# GongxunZhukong.net
KiCad netlist of a schematic drawn in Altium Designer
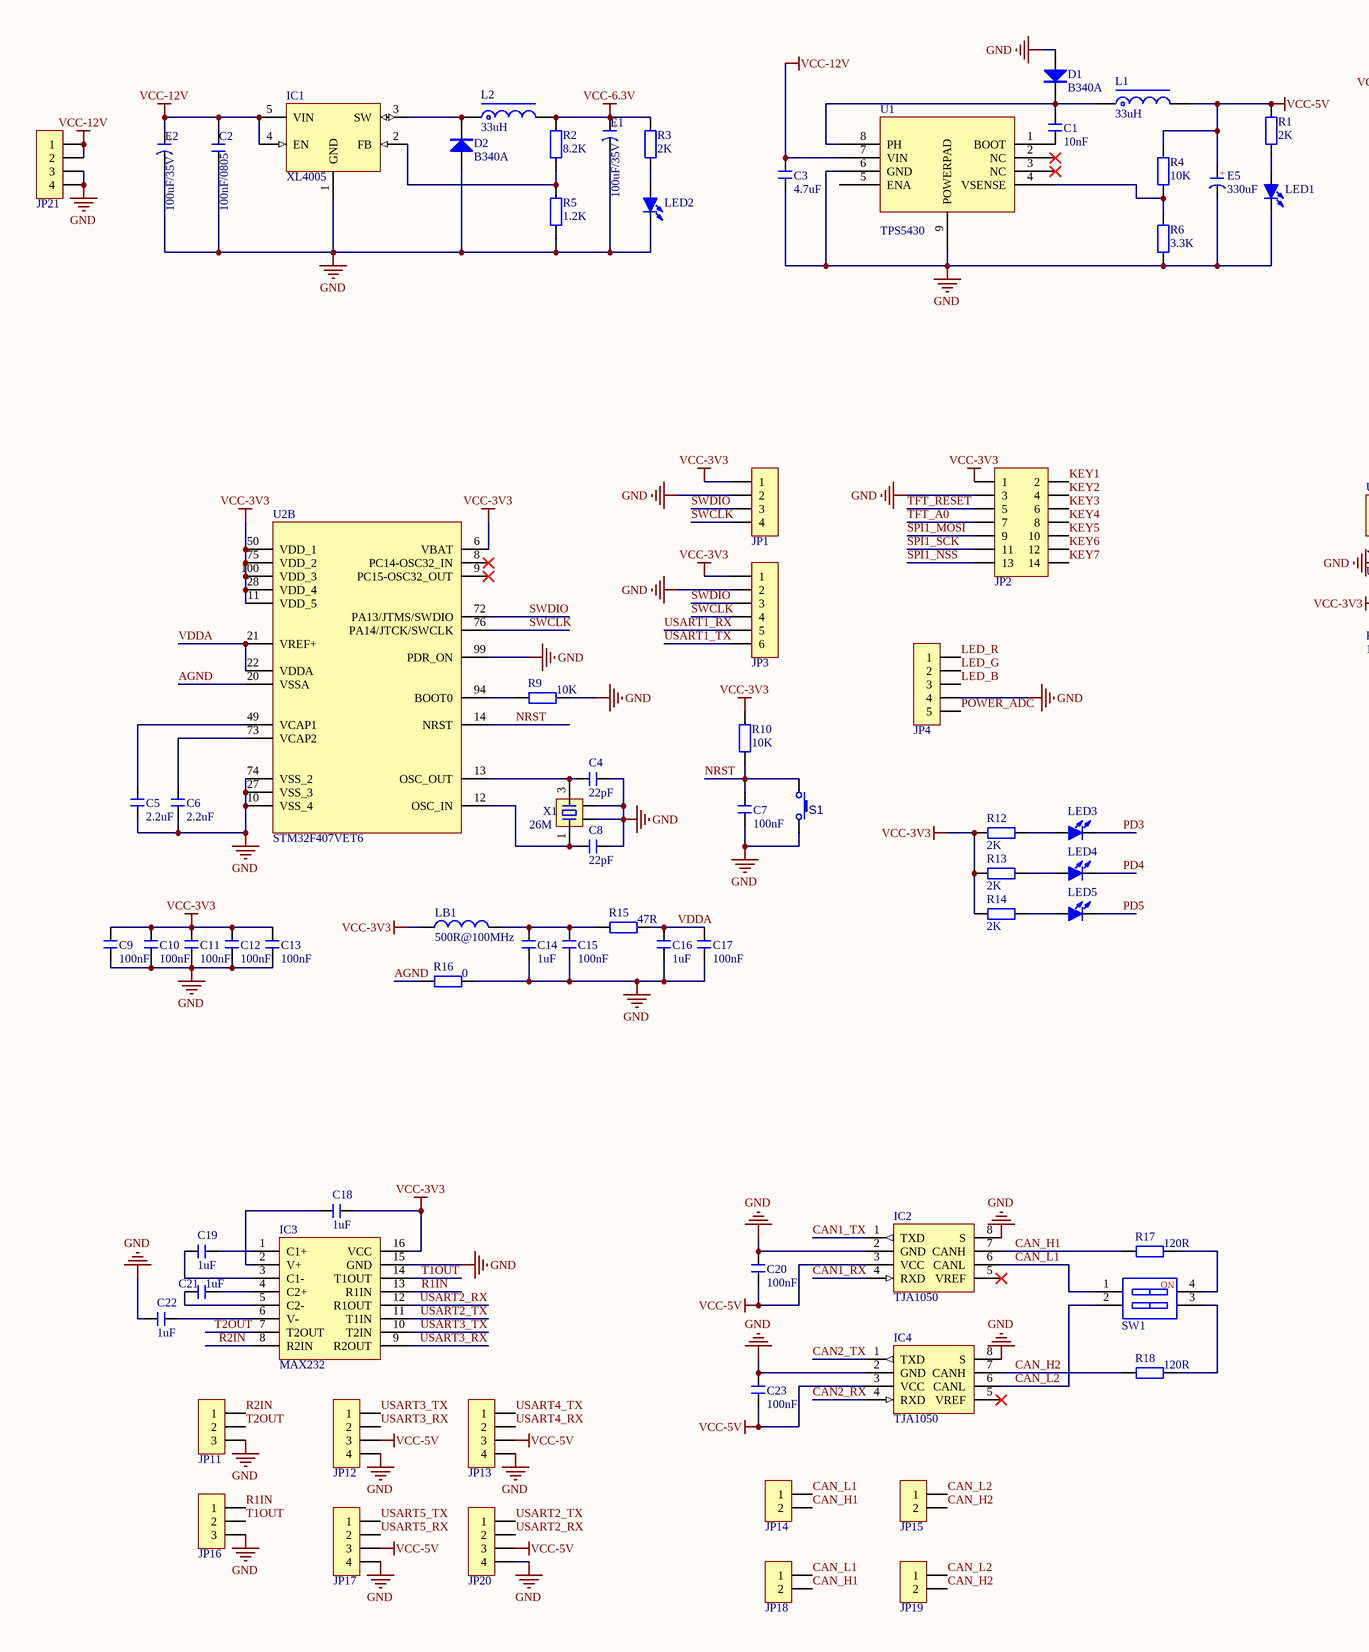
[diagram p0: GongxunZhukong.SchDoc, left]
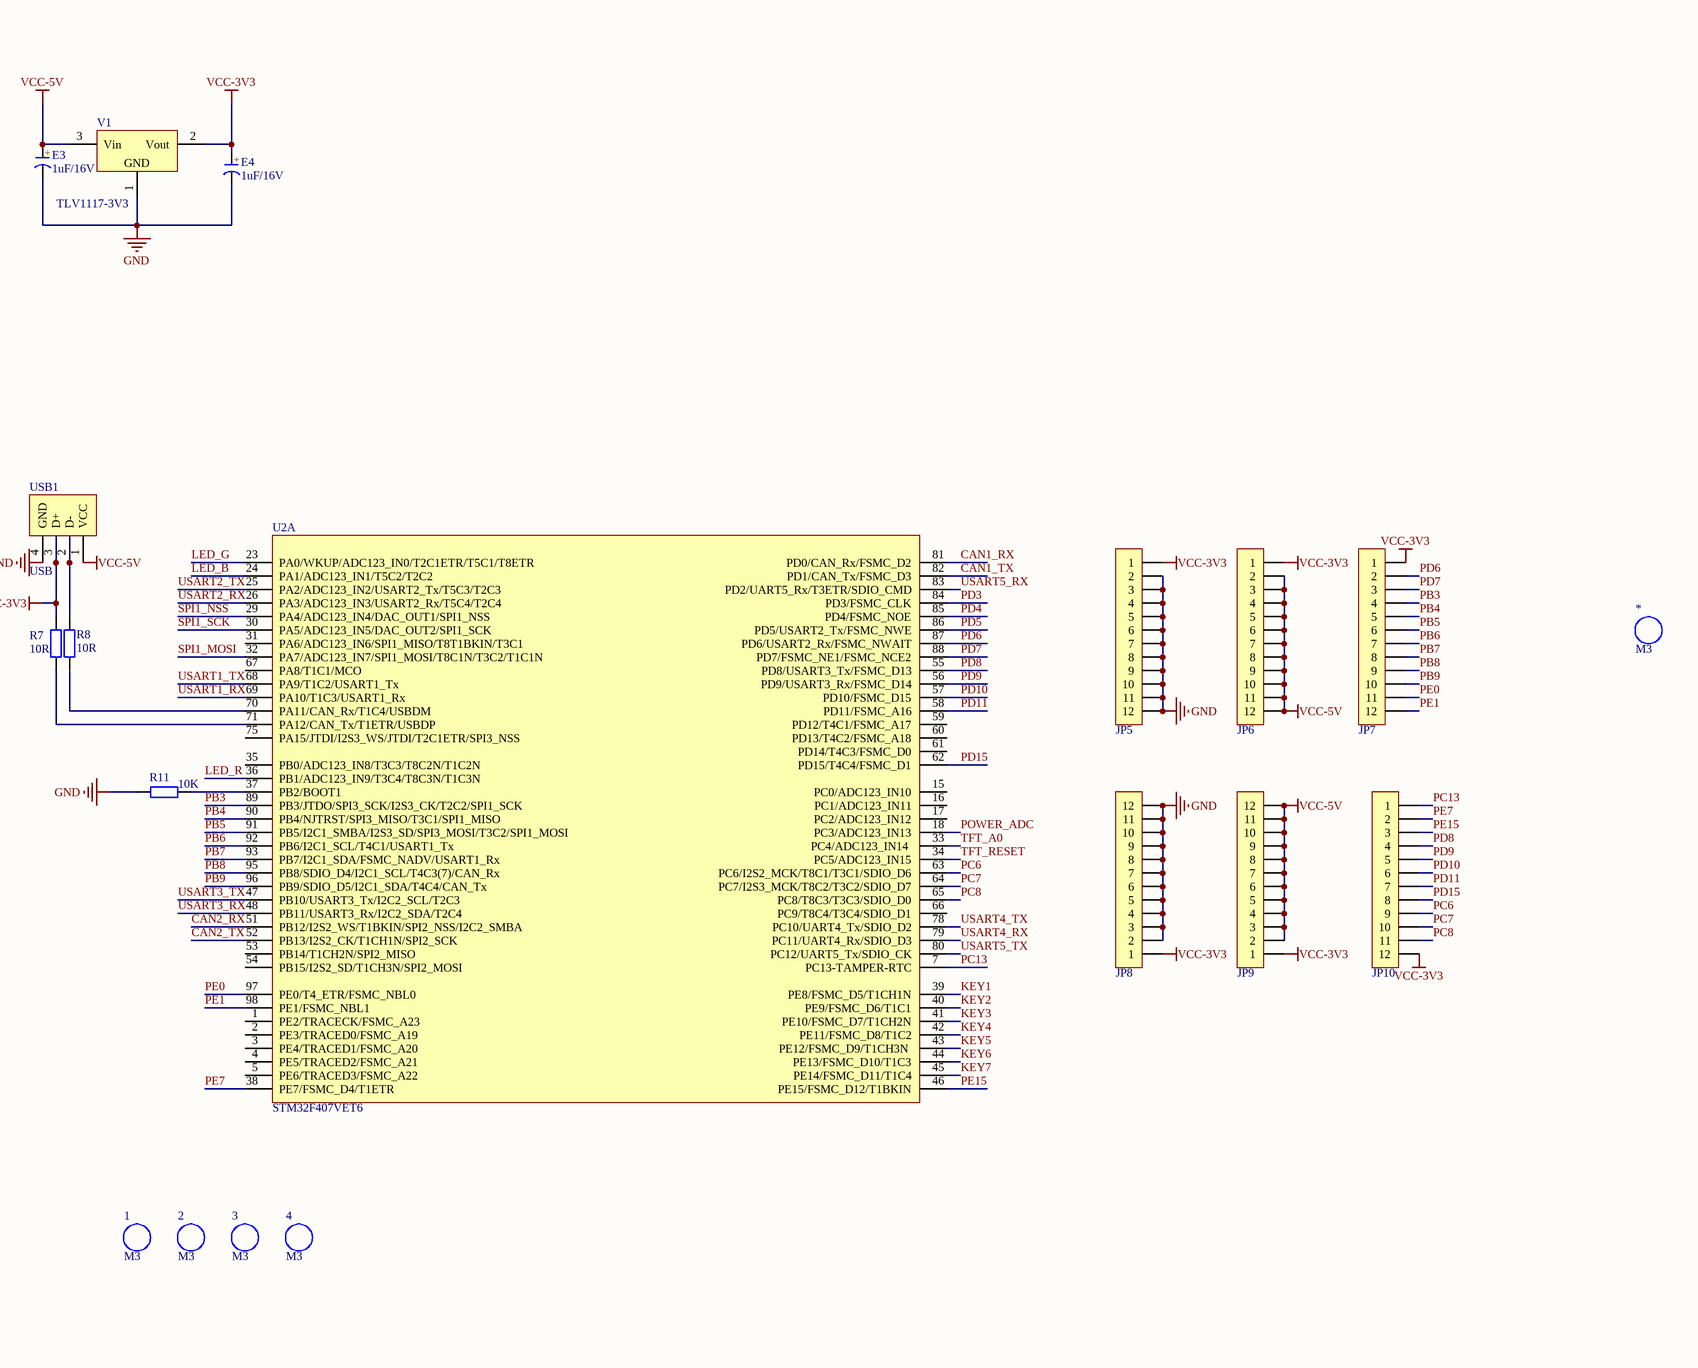
[diagram p1: GongxunZhukong.SchDoc, right]

(export (version "E")
  (design (tool "Eeschema 10.0.6"))
  (components
    (comp (ref "*")
      (value "M3")
      (footprint "M3 125X200")
      (description "铜柱孔")
      (libsource (lib "15.1 - 未分类器件") (part "M3"))
    )
    (comp (ref "1")
      (value "M3")
      (footprint "M3 125X200")
      (description "铜柱孔")
      (libsource (lib "15.1 - 未分类器件") (part "M3"))
    )
    (comp (ref "2")
      (value "M3")
      (footprint "M3 125X200")
      (description "铜柱孔")
      (libsource (lib "15.1 - 未分类器件") (part "M3"))
    )
    (comp (ref "3")
      (value "M3")
      (footprint "M3 125X200")
      (description "铜柱孔")
      (libsource (lib "15.1 - 未分类器件") (part "M3"))
    )
    (comp (ref "4")
      (value "M3")
      (footprint "M3 125X200")
      (description "铜柱孔")
      (libsource (lib "15.1 - 未分类器件") (part "M3"))
    )
    (comp (ref "C1")
      (value "10nF")
      (footprint "C 0603_M")
      (description "无极性贴片电容")
      (libsource (lib "3.1   - 电阻-电容-电感") (part "C"))
    )
    (comp (ref "C2")
      (value "100nF/0805")
      (footprint "C 0805_L")
      (description "无极性贴片电容")
      (libsource (lib "3.1   - 电阻-电容-电感") (part "C"))
    )
    (comp (ref "C3")
      (value "4.7uF")
      (footprint "C 0603_M")
      (description "无极性贴片电容")
      (libsource (lib "3.1   - 电阻-电容-电感") (part "C"))
    )
    (comp (ref "C4")
      (value "22pF")
      (footprint "C 0603_M")
      (description "无极性贴片电容")
      (libsource (lib "3.1   - 电阻-电容-电感") (part "C"))
    )
    (comp (ref "C5")
      (value "2.2uF")
      (footprint "C 0603_M")
      (description "无极性贴片电容")
      (libsource (lib "3.1   - 电阻-电容-电感") (part "C"))
    )
    (comp (ref "C6")
      (value "2.2uF")
      (footprint "C 0603_M")
      (description "无极性贴片电容")
      (libsource (lib "3.1   - 电阻-电容-电感") (part "C"))
    )
    (comp (ref "C7")
      (value "100nF")
      (footprint "C 0603_M")
      (description "无极性贴片电容")
      (libsource (lib "3.1   - 电阻-电容-电感") (part "C"))
    )
    (comp (ref "C8")
      (value "22pF")
      (footprint "C 0603_M")
      (description "无极性贴片电容")
      (libsource (lib "3.1   - 电阻-电容-电感") (part "C"))
    )
    (comp (ref "C9")
      (value "100nF")
      (footprint "C 0603_M")
      (description "无极性贴片电容")
      (libsource (lib "3.1   - 电阻-电容-电感") (part "C"))
    )
    (comp (ref "C10")
      (value "100nF")
      (footprint "C 0603_M")
      (description "无极性贴片电容")
      (libsource (lib "3.1   - 电阻-电容-电感") (part "C"))
    )
    (comp (ref "C11")
      (value "100nF")
      (footprint "C 0603_M")
      (description "无极性贴片电容")
      (libsource (lib "3.1   - 电阻-电容-电感") (part "C"))
    )
    (comp (ref "C12")
      (value "100nF")
      (footprint "C 0603_M")
      (description "无极性贴片电容")
      (libsource (lib "3.1   - 电阻-电容-电感") (part "C"))
    )
    (comp (ref "C13")
      (value "100nF")
      (footprint "C 0603_M")
      (description "无极性贴片电容")
      (libsource (lib "3.1   - 电阻-电容-电感") (part "C"))
    )
    (comp (ref "C14")
      (value "1uF")
      (footprint "C 0603_M")
      (description "无极性贴片电容")
      (libsource (lib "3.1   - 电阻-电容-电感") (part "C"))
    )
    (comp (ref "C15")
      (value "100nF")
      (footprint "C 0603_M")
      (description "无极性贴片电容")
      (libsource (lib "3.1   - 电阻-电容-电感") (part "C"))
    )
    (comp (ref "C16")
      (value "1uF")
      (footprint "C 0603_M")
      (description "无极性贴片电容")
      (libsource (lib "3.1   - 电阻-电容-电感") (part "C"))
    )
    (comp (ref "C17")
      (value "100nF")
      (footprint "C 0603_M")
      (description "无极性贴片电容")
      (libsource (lib "3.1   - 电阻-电容-电感") (part "C"))
    )
    (comp (ref "C18")
      (value "1uF")
      (footprint "C 0603_M")
      (description "无极性贴片电容")
      (libsource (lib "3.1   - 电阻-电容-电感") (part "C"))
    )
    (comp (ref "C19")
      (value "1uF")
      (footprint "C 0603_M")
      (description "无极性贴片电容")
      (libsource (lib "3.1   - 电阻-电容-电感") (part "C"))
    )
    (comp (ref "C20")
      (value "100nF")
      (footprint "C 0603_M")
      (description "无极性贴片电容")
      (libsource (lib "3.1   - 电阻-电容-电感") (part "C"))
    )
    (comp (ref "C21")
      (value "1uF")
      (footprint "C 0603_M")
      (description "无极性贴片电容")
      (libsource (lib "3.1   - 电阻-电容-电感") (part "C"))
    )
    (comp (ref "C22")
      (value "1uF")
      (footprint "C 0603_M")
      (description "无极性贴片电容")
      (libsource (lib "3.1   - 电阻-电容-电感") (part "C"))
    )
    (comp (ref "C23")
      (value "100nF")
      (footprint "C 0603_M")
      (description "无极性贴片电容")
      (libsource (lib "3.1   - 电阻-电容-电感") (part "C"))
    )
    (comp (ref "D1")
      (value "B340A")
      (footprint "SMA")
      (description "整流二极管")
      (libsource (lib "8.1   - 二极管-整流桥") (part "M7"))
    )
    (comp (ref "D2")
      (value "B340A")
      (footprint "SMA")
      (description "整流二极管")
      (libsource (lib "8.1   - 二极管-整流桥") (part "M7"))
    )
    (comp (ref "E1")
      (value "100uF/35V")
      (footprint "CM A(3*5.4)")
      (description "贴片电解电容")
      (libsource (lib "3.1   - 电阻-电容-电感") (part "C-CM"))
    )
    (comp (ref "E2")
      (value "100uF/35V")
      (footprint "CM A(3*5.4)")
      (description "贴片电解电容")
      (libsource (lib "3.1   - 电阻-电容-电感") (part "C-CM"))
    )
    (comp (ref "E3")
      (value "1uF/16V")
      (footprint "CD A(3216)")
      (description "贴片钽电容")
      (libsource (lib "3.1   - 电阻-电容-电感") (part "C-CD"))
    )
    (comp (ref "E4")
      (value "1uF/16V")
      (footprint "CD A(3216)")
      (description "贴片钽电容")
      (libsource (lib "3.1   - 电阻-电容-电感") (part "C-CD"))
    )
    (comp (ref "E5")
      (value "330uF")
      (footprint "CM D(6.3*7.7)")
      (description "贴片电解电容")
      (libsource (lib "3.1   - 电阻-电容-电感") (part "C-CM"))
    )
    (comp (ref "IC1")
      (value "XL4005")
      (footprint "TO263-5A")
      (description "DC降压芯片")
      (libsource (lib "1.3   - 电源类芯片") (part "XL4005"))
    )
    (comp (ref "IC2")
      (value "TJA1050")
      (footprint "SOP8_N")
      (description "CAN总线收发芯片")
      (libsource (lib "1.1   - IC芯片") (part "TJA1050"))
    )
    (comp (ref "IC3") (value "MAX232") (footprint "SOP16_N") (libsource (lib "1.1   - IC芯片") (part "MAX232")))
    (comp (ref "IC4")
      (value "TJA1050")
      (footprint "SOP8_N")
      (description "CAN总线收发芯片")
      (libsource (lib "1.1   - IC芯片") (part "TJA1050"))
    )
    (comp (ref "JP1")
      (value "HDR-1X4")
      (footprint "HDR2.54-LI-4P")
      (description "4P接插件")
      (libsource (lib "") (part "Header 4_1"))
    )
    (comp (ref "JP2")
      (value "Header 2X7")
      (footprint "HDR2.54-LI-2x7P")
      (description "7*2P接插件")
      (libsource (lib "4.6   - 接插件-脚距2.54") (part "Header 7X2"))
    )
    (comp (ref "JP3")
      (value "HDR-1X6")
      (footprint "PH2.0-WS-6P")
      (description "6P接插件")
      (libsource (lib "4.5   - 接插件-脚距2.0") (part "Header 6"))
    )
    (comp (ref "JP4")
      (value "HDR-1X5")
      (footprint "PH2.0-WS-5P")
      (description "5P接插件")
      (libsource (lib "4.5   - 接插件-脚距2.0") (part "Header 5"))
    )
    (comp (ref "JP5")
      (value "HDR-1X12")
      (footprint "HDR2.54-LI-12P")
      (description "12P接插件")
      (libsource (lib "") (part "Header 12_1"))
    )
    (comp (ref "JP6")
      (value "HDR-1X12")
      (footprint "HDR2.54-LI-12P")
      (description "12P接插件")
      (libsource (lib "") (part "Header 12_1"))
    )
    (comp (ref "JP7")
      (value "HDR-1X12")
      (footprint "HDR2.54-LI-12P")
      (description "12P接插件")
      (libsource (lib "") (part "Header 12_1"))
    )
    (comp (ref "JP8")
      (value "HDR-1X12")
      (footprint "HDR2.54-LI-12P")
      (description "12P接插件")
      (libsource (lib "4.6   - 接插件-脚距2.54") (part "Header 12"))
    )
    (comp (ref "JP9")
      (value "HDR-1X12")
      (footprint "HDR2.54-LI-12P")
      (description "12P接插件")
      (libsource (lib "4.6   - 接插件-脚距2.54") (part "Header 12"))
    )
    (comp (ref "JP10")
      (value "HDR-1X12")
      (footprint "HDR2.54-LI-12P")
      (description "12P接插件")
      (libsource (lib "") (part "Header 12_1"))
    )
    (comp (ref "JP11")
      (value "HDR-1X3")
      (footprint "PH2.0-WS-3P")
      (description "3P接插件")
      (libsource (lib "4.5   - 接插件-脚距2.0") (part "Header 3"))
    )
    (comp (ref "JP12")
      (value "HDR-1X4")
      (footprint "HDR2.54-LI-4P")
      (description "4P接插件")
      (libsource (lib "4.6   - 接插件-脚距2.54") (part "Header 4"))
    )
    (comp (ref "JP13")
      (value "HDR-1X4")
      (footprint "HDR2.54-LI-4P")
      (description "4P接插件")
      (libsource (lib "4.6   - 接插件-脚距2.54") (part "Header 4"))
    )
    (comp (ref "JP14")
      (value "HDR-1X2")
      (footprint "PH2.0-WS-2P")
      (description "2P接插件")
      (libsource (lib "4.5   - 接插件-脚距2.0") (part "Header 2"))
    )
    (comp (ref "JP15")
      (value "HDR-1X2")
      (footprint "PH2.0-WS-2P")
      (description "2P接插件")
      (libsource (lib "4.5   - 接插件-脚距2.0") (part "Header 2"))
    )
    (comp (ref "JP16")
      (value "HDR-1X3")
      (footprint "PH2.0-WS-3P")
      (description "3P接插件")
      (libsource (lib "4.5   - 接插件-脚距2.0") (part "Header 3"))
    )
    (comp (ref "JP17")
      (value "HDR-1X4")
      (footprint "HDR2.54-LI-4P")
      (description "4P接插件")
      (libsource (lib "4.6   - 接插件-脚距2.54") (part "Header 4"))
    )
    (comp (ref "JP18")
      (value "HDR-1X2")
      (footprint "PH2.0-WS-2P")
      (description "2P接插件")
      (libsource (lib "4.5   - 接插件-脚距2.0") (part "Header 2"))
    )
    (comp (ref "JP19")
      (value "HDR-1X2")
      (footprint "PH2.0-WS-2P")
      (description "2P接插件")
      (libsource (lib "4.5   - 接插件-脚距2.0") (part "Header 2"))
    )
    (comp (ref "JP20")
      (value "HDR-1X4")
      (footprint "PH2.0-WS-4P")
      (description "4P接插件")
      (libsource (lib "4.5   - 接插件-脚距2.0") (part "Header 4"))
    )
    (comp (ref "JP21")
      (value "HDR-1X4")
      (footprint "XH2.54-WS-4P")
      (description "4P接插件")
      (libsource (lib "4.6   - 接插件-脚距2.54") (part "Header 4"))
    )
    (comp (ref "L1")
      (value "33uH")
      (footprint "CDRH74")
      (description "功率屏蔽电感")
      (libsource (lib "3.1   - 电阻-电容-电感") (part "L-CDRH"))
    )
    (comp (ref "L2")
      (value "33uH")
      (footprint "CDRH74")
      (description "功率屏蔽电感")
      (libsource (lib "3.1   - 电阻-电容-电感") (part "L-CDRH"))
    )
    (comp (ref "LB1")
      (value "500R@100MHz")
      (footprint "FB 0603_M")
      (description "磁珠")
      (libsource (lib "3.1   - 电阻-电容-电感") (part "LB"))
    )
    (comp (ref "LED1")
      (value "~")
      (footprint "LED 0603B")
      (description "贴片LED")
      (libsource (lib "9.1   - LED") (part "LED-SMD"))
    )
    (comp (ref "LED2")
      (value "~")
      (footprint "LED 0603B")
      (description "贴片LED")
      (libsource (lib "9.1   - LED") (part "LED-SMD"))
    )
    (comp (ref "LED3")
      (value "~")
      (footprint "LED 0603B")
      (description "贴片LED")
      (libsource (lib "9.1   - LED") (part "LED-SMD"))
    )
    (comp (ref "LED4")
      (value "~")
      (footprint "LED 0603B")
      (description "贴片LED")
      (libsource (lib "9.1   - LED") (part "LED-SMD"))
    )
    (comp (ref "LED5")
      (value "~")
      (footprint "LED 0603B")
      (description "贴片LED")
      (libsource (lib "9.1   - LED") (part "LED-SMD"))
    )
    (comp (ref "R1")
      (value "2K")
      (footprint "R 0603_M")
      (description "贴片电阻")
      (libsource (lib "3.1   - 电阻-电容-电感") (part "R"))
    )
    (comp (ref "R2")
      (value "8.2K")
      (footprint "R 0603_M")
      (description "贴片电阻")
      (libsource (lib "3.1   - 电阻-电容-电感") (part "R"))
    )
    (comp (ref "R3")
      (value "2K")
      (footprint "R 0603_M")
      (description "贴片电阻")
      (libsource (lib "3.1   - 电阻-电容-电感") (part "R"))
    )
    (comp (ref "R4")
      (value "10K")
      (footprint "R 0603_M")
      (description "贴片电阻")
      (libsource (lib "3.1   - 电阻-电容-电感") (part "R"))
    )
    (comp (ref "R5")
      (value "1.2K")
      (footprint "R 0603_M")
      (description "贴片电阻")
      (libsource (lib "3.1   - 电阻-电容-电感") (part "R"))
    )
    (comp (ref "R6")
      (value "3.3K")
      (footprint "R 0603_M")
      (description "贴片电阻")
      (libsource (lib "3.1   - 电阻-电容-电感") (part "R"))
    )
    (comp (ref "R7")
      (value "10R")
      (footprint "R 0603_M")
      (description "贴片电阻")
      (libsource (lib "3.1   - 电阻-电容-电感") (part "R"))
    )
    (comp (ref "R8")
      (value "10R")
      (footprint "R 0603_M")
      (description "贴片电阻")
      (libsource (lib "3.1   - 电阻-电容-电感") (part "R"))
    )
    (comp (ref "R9")
      (value "10K")
      (footprint "R 0603_M")
      (description "贴片电阻")
      (libsource (lib "3.1   - 电阻-电容-电感") (part "R"))
    )
    (comp (ref "R10")
      (value "10K")
      (footprint "R 0603_M")
      (description "贴片电阻")
      (libsource (lib "3.1   - 电阻-电容-电感") (part "R"))
    )
    (comp (ref "R11")
      (value "10K")
      (footprint "R 0603_M")
      (description "贴片电阻")
      (libsource (lib "3.1   - 电阻-电容-电感") (part "R"))
    )
    (comp (ref "R12")
      (value "2K")
      (footprint "R 0603_M")
      (description "贴片电阻")
      (libsource (lib "3.1   - 电阻-电容-电感") (part "R"))
    )
    (comp (ref "R13")
      (value "2K")
      (footprint "R 0603_M")
      (description "贴片电阻")
      (libsource (lib "3.1   - 电阻-电容-电感") (part "R"))
    )
    (comp (ref "R14")
      (value "2K")
      (footprint "R 0603_M")
      (description "贴片电阻")
      (libsource (lib "3.1   - 电阻-电容-电感") (part "R"))
    )
    (comp (ref "R15")
      (value "47R")
      (footprint "R 0603_M")
      (description "贴片电阻")
      (libsource (lib "3.1   - 电阻-电容-电感") (part "R"))
    )
    (comp (ref "R16")
      (value "0")
      (footprint "R 0603_M")
      (description "贴片电阻")
      (libsource (lib "3.1   - 电阻-电容-电感") (part "R"))
    )
    (comp (ref "R17")
      (value "120R")
      (footprint "R 0603_M")
      (description "贴片电阻")
      (libsource (lib "3.1   - 电阻-电容-电感") (part "R"))
    )
    (comp (ref "R18")
      (value "120R")
      (footprint "R 0603_M")
      (description "贴片电阻")
      (libsource (lib "3.1   - 电阻-电容-电感") (part "R"))
    )
    (comp (ref "S1")
      (value "Button")
      (footprint "PTS810-3*4-CurvePin")
      (description "按键")
      (fields (field (name "PUBLISHER") "Altium Limited"))
      (libsource (lib "5.1   - 按键-开关") (part "KEY"))
    )
    (comp (ref "SW1")
      (value "CSW-2P")
      (footprint "CSW1.27 SMD-2P")
      (description "2路编码开关")
      (libsource (lib "5.1   - 按键-开关") (part "CSW-2P"))
    )
    (comp (ref "U1")
      (value "TPS5430")
      (footprint "ESOP8_M")
      (libsource (lib "STM32G474VET6") (part "TPS5430"))
    )
    (comp (ref "U2")
      (value "STM32F407VET6")
      (footprint "LQFP100 14x14_L")
      (libsource (lib "2.1   - STM32系列单片机") (part "STM32F407VET6"))
    )
    (comp (ref "USB1")
      (value "USB")
      (footprint "USB-A/S_A")
      (description "USB-A型母接口")
      (libsource (lib "4.1   - 接口类") (part "USB-A/S"))
    )
    (comp (ref "V1")
      (value "TLV1117-3V3")
      (footprint "SOT223_N")
      (description "三端稳压芯片")
      (libsource (lib "1.3   - 电源类芯片") (part "AMS1117"))
    )
    (comp (ref "X1")
      (value "26M")
      (footprint "OSC 3225-4P")
      (description "4脚无源晶振")
      (libsource (lib "10.1 - 保险丝-晶振") (part "XTAL-4P"))
    )
  )
  (nets
    (net (code "1") (name "/AGND") (class "Default")
      (node (ref "R16") (pin "2") (pinfunction "2_2") (pintype "passive"))
      (node (ref "U2") (pin "20") (pinfunction "VSSA_20") (pintype "passive"))
    )
    (net (code "2") (name "/CAN1_RX") (class "Default")
      (node (ref "IC2") (pin "4") (pinfunction "RXD_4") (pintype "input"))
      (node (ref "U2") (pin "81") (pinfunction "PD0/CAN_Rx/FSMC_D2_81") (pintype "passive"))
    )
    (net (code "3") (name "/CAN1_TX") (class "Default")
      (node (ref "IC2") (pin "1") (pinfunction "TXD_1") (pintype "output"))
      (node (ref "U2") (pin "82") (pinfunction "PD1/CAN_Tx/FSMC_D3_82") (pintype "passive"))
    )
    (net (code "4") (name "/CAN2_RX") (class "Default")
      (node (ref "IC4") (pin "4") (pinfunction "RXD_4") (pintype "input"))
      (node (ref "U2") (pin "51") (pinfunction "PB12/I2S2_WS/T1BKIN/SPI2_NSS/I2C2_SMBA_51") (pintype "passive"))
    )
    (net (code "5") (name "/CAN2_TX") (class "Default")
      (node (ref "IC4") (pin "1") (pinfunction "TXD_1") (pintype "output"))
      (node (ref "U2") (pin "52") (pinfunction "PB13/I2S2_CK/T1CH1N/SPI2_SCK_52") (pintype "passive"))
    )
    (net (code "6") (name "/CAN_H1") (class "Default")
      (node (ref "IC2") (pin "7") (pinfunction "CANH_7") (pintype "passive"))
      (node (ref "JP14") (pin "2") (pinfunction "2_2") (pintype "passive"))
      (node (ref "JP18") (pin "2") (pinfunction "2_2") (pintype "passive"))
      (node (ref "R17") (pin "2") (pinfunction "2_2") (pintype "passive"))
    )
    (net (code "7") (name "/CAN_H2") (class "Default")
      (node (ref "IC4") (pin "7") (pinfunction "CANH_7") (pintype "passive"))
      (node (ref "JP15") (pin "2") (pinfunction "2_2") (pintype "passive"))
      (node (ref "JP19") (pin "2") (pinfunction "2_2") (pintype "passive"))
      (node (ref "R18") (pin "2") (pinfunction "2_2") (pintype "passive"))
    )
    (net (code "8") (name "/CAN_L1") (class "Default")
      (node (ref "IC2") (pin "6") (pinfunction "CANL_6") (pintype "passive"))
      (node (ref "JP14") (pin "1") (pinfunction "1_1") (pintype "passive"))
      (node (ref "JP18") (pin "1") (pinfunction "1_1") (pintype "passive"))
      (node (ref "SW1") (pin "1") (pinfunction "1_1") (pintype "passive"))
    )
    (net (code "9") (name "/CAN_L2") (class "Default")
      (node (ref "IC4") (pin "6") (pinfunction "CANL_6") (pintype "passive"))
      (node (ref "JP15") (pin "1") (pinfunction "1_1") (pintype "passive"))
      (node (ref "JP19") (pin "1") (pinfunction "1_1") (pintype "passive"))
      (node (ref "SW1") (pin "2") (pinfunction "2_2") (pintype "passive"))
    )
    (net (code "10") (name "/KEY1") (class "Default")
      (node (ref "JP2") (pin "2") (pinfunction "2_2") (pintype "passive"))
      (node (ref "U2") (pin "39") (pinfunction "PE8/FSMC_D5/T1CH1N_39") (pintype "passive"))
    )
    (net (code "11") (name "/KEY2") (class "Default")
      (node (ref "JP2") (pin "4") (pinfunction "4_4") (pintype "passive"))
      (node (ref "U2") (pin "40") (pinfunction "PE9/FSMC_D6/T1C1_40") (pintype "passive"))
    )
    (net (code "12") (name "/KEY3") (class "Default")
      (node (ref "JP2") (pin "6") (pinfunction "6_6") (pintype "passive"))
      (node (ref "U2") (pin "41") (pinfunction "PE10/FSMC_D7/T1CH2N_41") (pintype "passive"))
    )
    (net (code "13") (name "/KEY4") (class "Default")
      (node (ref "JP2") (pin "8") (pinfunction "8_8") (pintype "passive"))
      (node (ref "U2") (pin "42") (pinfunction "PE11/FSMC_D8/T1C2_42") (pintype "passive"))
    )
    (net (code "14") (name "/KEY5") (class "Default")
      (node (ref "JP2") (pin "10") (pinfunction "10_10") (pintype "passive"))
      (node (ref "U2") (pin "43") (pinfunction "PE12/FSMC_D9/T1CH3N_43") (pintype "passive"))
    )
    (net (code "15") (name "/KEY6") (class "Default")
      (node (ref "JP2") (pin "12") (pinfunction "12_12") (pintype "passive"))
      (node (ref "U2") (pin "44") (pinfunction "PE13/FSMC_D10/T1C3_44") (pintype "passive"))
    )
    (net (code "16") (name "/KEY7") (class "Default")
      (node (ref "JP2") (pin "14") (pinfunction "14_14") (pintype "passive"))
      (node (ref "U2") (pin "45") (pinfunction "PE14/FSMC_D11/T1C4_45") (pintype "passive"))
    )
    (net (code "17") (name "/LED_B") (class "Default")
      (node (ref "JP4") (pin "3") (pinfunction "3_3") (pintype "passive"))
      (node (ref "U2") (pin "24") (pinfunction "PA1/ADC123_IN1/T5C2/T2C2_24") (pintype "passive"))
    )
    (net (code "18") (name "/LED_G") (class "Default")
      (node (ref "JP4") (pin "2") (pinfunction "2_2") (pintype "passive"))
      (node (ref "U2") (pin "23") (pinfunction "PA0/WKUP/ADC123_IN0/T2C1ETR/T5C1/T8ETR_23") (pintype "passive"))
    )
    (net (code "19") (name "/LED_R") (class "Default")
      (node (ref "JP4") (pin "1") (pinfunction "1_1") (pintype "passive"))
      (node (ref "U2") (pin "36") (pinfunction "PB1/ADC123_IN9/T3C4/T8C3N/T1C3N_36") (pintype "passive"))
    )
    (net (code "20") (name "/NRST") (class "Default")
      (node (ref "C7") (pin "1") (pinfunction "1_1") (pintype "passive"))
      (node (ref "R10") (pin "2") (pinfunction "2_2") (pintype "passive"))
      (node (ref "S1") (pin "2") (pinfunction "2_2") (pintype "passive"))
      (node (ref "U2") (pin "14") (pinfunction "NRST_14") (pintype "passive"))
    )
    (net (code "21") (name "/PB3") (class "Default")
      (node (ref "JP7") (pin "4") (pinfunction "4_4") (pintype "passive"))
      (node (ref "U2") (pin "89") (pinfunction "PB3/JTDO/SPI3_SCK/I2S3_CK/T2C2/SPI1_SCK_89") (pintype "passive"))
    )
    (net (code "22") (name "/PB4") (class "Default")
      (node (ref "JP7") (pin "5") (pinfunction "5_5") (pintype "passive"))
      (node (ref "U2") (pin "90") (pinfunction "PB4/NJTRST/SPI3_MISO/T3C1/SPI1_MISO_90") (pintype "passive"))
    )
    (net (code "23") (name "/PB5") (class "Default")
      (node (ref "JP7") (pin "6") (pinfunction "6_6") (pintype "passive"))
      (node (ref "U2") (pin "91") (pinfunction "PB5/I2C1_SMBA/I2S3_SD/SPI3_MOSI/T3C2/SPI1_MOSI_91") (pintype "passive"))
    )
    (net (code "24") (name "/PB6") (class "Default")
      (node (ref "JP7") (pin "7") (pinfunction "7_7") (pintype "passive"))
      (node (ref "U2") (pin "92") (pinfunction "PB6/I2C1_SCL/T4C1/USART1_Tx_92") (pintype "passive"))
    )
    (net (code "25") (name "/PB7") (class "Default")
      (node (ref "JP7") (pin "8") (pinfunction "8_8") (pintype "passive"))
      (node (ref "U2") (pin "93") (pinfunction "PB7/I2C1_SDA/FSMC_NADV/USART1_Rx_93") (pintype "passive"))
    )
    (net (code "26") (name "/PB8") (class "Default")
      (node (ref "JP7") (pin "9") (pinfunction "9_9") (pintype "passive"))
      (node (ref "U2") (pin "95") (pinfunction "PB8/SDIO_D4/I2C1_SCL/T4C3(7)/CAN_Rx_95") (pintype "passive"))
    )
    (net (code "27") (name "/PB9") (class "Default")
      (node (ref "JP7") (pin "10") (pinfunction "10_10") (pintype "passive"))
      (node (ref "U2") (pin "96") (pinfunction "PB9/SDIO_D5/I2C1_SDA/T4C4/CAN_Tx_96") (pintype "passive"))
    )
    (net (code "28") (name "/PC6") (class "Default")
      (node (ref "JP10") (pin "9") (pinfunction "9_9") (pintype "passive"))
      (node (ref "U2") (pin "63") (pinfunction "PC6/I2S2_MCK/T8C1/T3C1/SDIO_D6_63") (pintype "passive"))
    )
    (net (code "29") (name "/PC7") (class "Default")
      (node (ref "JP10") (pin "10") (pinfunction "10_10") (pintype "passive"))
      (node (ref "U2") (pin "64") (pinfunction "PC7/I2S3_MCK/T8C2/T3C2/SDIO_D7_64") (pintype "passive"))
    )
    (net (code "30") (name "/PC8") (class "Default")
      (node (ref "JP10") (pin "11") (pinfunction "11_11") (pintype "passive"))
      (node (ref "U2") (pin "65") (pinfunction "PC8/T8C3/T3C3/SDIO_D0_65") (pintype "passive"))
    )
    (net (code "31") (name "/PC13") (class "Default")
      (node (ref "JP10") (pin "1") (pinfunction "1_1") (pintype "passive"))
      (node (ref "U2") (pin "7") (pinfunction "PC13-TAMPER-RTC_7") (pintype "passive"))
    )
    (net (code "32") (name "/PD3") (class "Default")
      (node (ref "LED3") (pin "2") (pinfunction "K_2") (pintype "passive"))
      (node (ref "U2") (pin "84") (pinfunction "PD3/FSMC_CLK_84") (pintype "passive"))
    )
    (net (code "33") (name "/PD4") (class "Default")
      (node (ref "LED4") (pin "2") (pinfunction "K_2") (pintype "passive"))
      (node (ref "U2") (pin "85") (pinfunction "PD4/FSMC_NOE_85") (pintype "passive"))
    )
    (net (code "34") (name "/PD5") (class "Default")
      (node (ref "LED5") (pin "2") (pinfunction "K_2") (pintype "passive"))
      (node (ref "U2") (pin "86") (pinfunction "PD5/USART2_Tx/FSMC_NWE_86") (pintype "passive"))
    )
    (net (code "35") (name "/PD6") (class "Default")
      (node (ref "JP7") (pin "2") (pinfunction "2_2") (pintype "passive"))
      (node (ref "U2") (pin "87") (pinfunction "PD6/USART2_Rx/FSMC_NWAIT_87") (pintype "passive"))
    )
    (net (code "36") (name "/PD7") (class "Default")
      (node (ref "JP7") (pin "3") (pinfunction "3_3") (pintype "passive"))
      (node (ref "U2") (pin "88") (pinfunction "PD7/FSMC_NE1/FSMC_NCE2_88") (pintype "passive"))
    )
    (net (code "37") (name "/PD8") (class "Default")
      (node (ref "JP10") (pin "4") (pinfunction "4_4") (pintype "passive"))
      (node (ref "U2") (pin "55") (pinfunction "PD8/USART3_Tx/FSMC_D13_55") (pintype "passive"))
    )
    (net (code "38") (name "/PD9") (class "Default")
      (node (ref "JP10") (pin "5") (pinfunction "5_5") (pintype "passive"))
      (node (ref "U2") (pin "56") (pinfunction "PD9/USART3_Rx/FSMC_D14_56") (pintype "passive"))
    )
    (net (code "39") (name "/PD10") (class "Default")
      (node (ref "JP10") (pin "6") (pinfunction "6_6") (pintype "passive"))
      (node (ref "U2") (pin "57") (pinfunction "PD10/FSMC_D15_57") (pintype "passive"))
    )
    (net (code "40") (name "/PD11") (class "Default")
      (node (ref "JP10") (pin "7") (pinfunction "7_7") (pintype "passive"))
      (node (ref "U2") (pin "58") (pinfunction "PD11/FSMC_A16_58") (pintype "passive"))
    )
    (net (code "41") (name "/PD15") (class "Default")
      (node (ref "JP10") (pin "8") (pinfunction "8_8") (pintype "passive"))
      (node (ref "U2") (pin "62") (pinfunction "PD15/T4C4/FSMC_D1_62") (pintype "passive"))
    )
    (net (code "42") (name "/PE0") (class "Default")
      (node (ref "JP7") (pin "11") (pinfunction "11_11") (pintype "passive"))
      (node (ref "U2") (pin "97") (pinfunction "PE0/T4_ETR/FSMC_NBL0_97") (pintype "passive"))
    )
    (net (code "43") (name "/PE1") (class "Default")
      (node (ref "JP7") (pin "12") (pinfunction "12_12") (pintype "passive"))
      (node (ref "U2") (pin "98") (pinfunction "PE1/FSMC_NBL1_98") (pintype "passive"))
    )
    (net (code "44") (name "/PE7") (class "Default")
      (node (ref "JP10") (pin "2") (pinfunction "2_2") (pintype "passive"))
      (node (ref "U2") (pin "38") (pinfunction "PE7/FSMC_D4/T1ETR_38") (pintype "passive"))
    )
    (net (code "45") (name "/PE15") (class "Default")
      (node (ref "JP10") (pin "3") (pinfunction "3_3") (pintype "passive"))
      (node (ref "U2") (pin "46") (pinfunction "PE15/FSMC_D12/T1BKIN_46") (pintype "passive"))
    )
    (net (code "46") (name "/POWER_ADC") (class "Default")
      (node (ref "JP4") (pin "5") (pinfunction "5_5") (pintype "passive"))
      (node (ref "U2") (pin "18") (pinfunction "PC3/ADC123_IN13_18") (pintype "passive"))
    )
    (net (code "47") (name "/R1IN") (class "Default")
      (node (ref "IC3") (pin "13") (pinfunction "R1IN_13") (pintype "passive"))
      (node (ref "JP16") (pin "1") (pinfunction "1_1") (pintype "passive"))
    )
    (net (code "48") (name "/R2IN") (class "Default")
      (node (ref "IC3") (pin "8") (pinfunction "R2IN_8") (pintype "passive"))
      (node (ref "JP11") (pin "1") (pinfunction "1_1") (pintype "passive"))
    )
    (net (code "49") (name "/SPI1_MOSI") (class "Default")
      (node (ref "JP2") (pin "9") (pinfunction "9_9") (pintype "passive"))
      (node (ref "U2") (pin "32") (pinfunction "PA7/ADC123_IN7/SPI1_MOSI/T8C1N/T3C2/T1C1N_32") (pintype "passive"))
    )
    (net (code "50") (name "/SPI1_NSS") (class "Default")
      (node (ref "JP2") (pin "13") (pinfunction "13_13") (pintype "passive"))
      (node (ref "U2") (pin "29") (pinfunction "PA4/ADC123_IN4/DAC_OUT1/SPI1_NSS_29") (pintype "passive"))
    )
    (net (code "51") (name "/SPI1_SCK") (class "Default")
      (node (ref "JP2") (pin "11") (pinfunction "11_11") (pintype "passive"))
      (node (ref "U2") (pin "30") (pinfunction "PA5/ADC123_IN5/DAC_OUT2/SPI1_SCK_30") (pintype "passive"))
    )
    (net (code "52") (name "/SWCLK") (class "Default")
      (node (ref "JP1") (pin "4") (pinfunction "4_4") (pintype "passive"))
      (node (ref "JP3") (pin "4") (pinfunction "4_4") (pintype "passive"))
      (node (ref "U2") (pin "76") (pinfunction "PA14/JTCK/SWCLK_76") (pintype "passive"))
    )
    (net (code "53") (name "/SWDIO") (class "Default")
      (node (ref "JP1") (pin "3") (pinfunction "3_3") (pintype "passive"))
      (node (ref "JP3") (pin "3") (pinfunction "3_3") (pintype "passive"))
      (node (ref "U2") (pin "72") (pinfunction "PA13/JTMS/SWDIO_72") (pintype "passive"))
    )
    (net (code "54") (name "/T1OUT") (class "Default")
      (node (ref "IC3") (pin "14") (pinfunction "T1OUT_14") (pintype "passive"))
      (node (ref "JP16") (pin "2") (pinfunction "2_2") (pintype "passive"))
    )
    (net (code "55") (name "/T2OUT") (class "Default")
      (node (ref "IC3") (pin "7") (pinfunction "T2OUT_7") (pintype "passive"))
      (node (ref "JP11") (pin "2") (pinfunction "2_2") (pintype "passive"))
    )
    (net (code "56") (name "/TFT_A0") (class "Default")
      (node (ref "JP2") (pin "7") (pinfunction "7_7") (pintype "passive"))
      (node (ref "U2") (pin "33") (pinfunction "PC4/ADC123_IN14_33") (pintype "passive"))
    )
    (net (code "57") (name "/TFT_RESET") (class "Default")
      (node (ref "JP2") (pin "5") (pinfunction "5_5") (pintype "passive"))
      (node (ref "U2") (pin "34") (pinfunction "PC5/ADC123_IN15_34") (pintype "passive"))
    )
    (net (code "58") (name "/USART1_RX") (class "Default")
      (node (ref "JP3") (pin "5") (pinfunction "5_5") (pintype "passive"))
      (node (ref "U2") (pin "69") (pinfunction "PA10/T1C3/USART1_Rx_69") (pintype "passive"))
    )
    (net (code "59") (name "/USART1_TX") (class "Default")
      (node (ref "JP3") (pin "6") (pinfunction "6_6") (pintype "passive"))
      (node (ref "U2") (pin "68") (pinfunction "PA9/T1C2/USART1_Tx_68") (pintype "passive"))
    )
    (net (code "60") (name "/USART2_RX") (class "Default")
      (node (ref "IC3") (pin "12") (pinfunction "R1OUT_12") (pintype "passive"))
      (node (ref "JP20") (pin "2") (pinfunction "2_2") (pintype "passive"))
      (node (ref "U2") (pin "26") (pinfunction "PA3/ADC123_IN3/USART2_Rx/T5C4/T2C4_26") (pintype "passive"))
    )
    (net (code "61") (name "/USART2_TX") (class "Default")
      (node (ref "IC3") (pin "11") (pinfunction "T1IN_11") (pintype "passive"))
      (node (ref "JP20") (pin "1") (pinfunction "1_1") (pintype "passive"))
      (node (ref "U2") (pin "25") (pinfunction "PA2/ADC123_IN2/USART2_Tx/T5C3/T2C3_25") (pintype "passive"))
    )
    (net (code "62") (name "/USART3_RX") (class "Default")
      (node (ref "IC3") (pin "9") (pinfunction "R2OUT_9") (pintype "passive"))
      (node (ref "JP12") (pin "2") (pinfunction "2_2") (pintype "passive"))
      (node (ref "U2") (pin "48") (pinfunction "PB11/USART3_Rx/I2C2_SDA/T2C4_48") (pintype "passive"))
    )
    (net (code "63") (name "/USART3_TX") (class "Default")
      (node (ref "IC3") (pin "10") (pinfunction "T2IN_10") (pintype "passive"))
      (node (ref "JP12") (pin "1") (pinfunction "1_1") (pintype "passive"))
      (node (ref "U2") (pin "47") (pinfunction "PB10/USART3_Tx/I2C2_SCL/T2C3_47") (pintype "passive"))
    )
    (net (code "64") (name "/USART4_RX") (class "Default")
      (node (ref "JP13") (pin "2") (pinfunction "2_2") (pintype "passive"))
      (node (ref "U2") (pin "79") (pinfunction "PC11/UART4_Rx/SDIO_D3_79") (pintype "passive"))
    )
    (net (code "65") (name "/USART4_TX") (class "Default")
      (node (ref "JP13") (pin "1") (pinfunction "1_1") (pintype "passive"))
      (node (ref "U2") (pin "78") (pinfunction "PC10/UART4_Tx/SDIO_D2_78") (pintype "passive"))
    )
    (net (code "66") (name "/USART5_RX") (class "Default")
      (node (ref "JP17") (pin "2") (pinfunction "2_2") (pintype "passive"))
      (node (ref "U2") (pin "83") (pinfunction "PD2/UART5_Rx/T3ETR/SDIO_CMD_83") (pintype "passive"))
    )
    (net (code "67") (name "/USART5_TX") (class "Default")
      (node (ref "JP17") (pin "1") (pinfunction "1_1") (pintype "passive"))
      (node (ref "U2") (pin "80") (pinfunction "PC12/UART5_Tx/SDIO_CK_80") (pintype "passive"))
    )
    (net (code "68") (name "/VDDA") (class "Default")
      (node (ref "C16") (pin "1") (pinfunction "1_1") (pintype "passive"))
      (node (ref "C17") (pin "1") (pinfunction "1_1") (pintype "passive"))
      (node (ref "R15") (pin "1") (pinfunction "1_1") (pintype "passive"))
      (node (ref "U2") (pin "21") (pinfunction "VREF+_21") (pintype "passive"))
      (node (ref "U2") (pin "22") (pinfunction "VDDA_22") (pintype "passive"))
    )
    (net (code "69") (name "GND") (class "Default")
      (node (ref "C10") (pin "2") (pinfunction "2_2") (pintype "passive"))
      (node (ref "C11") (pin "2") (pinfunction "2_2") (pintype "passive"))
      (node (ref "C12") (pin "2") (pinfunction "2_2") (pintype "passive"))
      (node (ref "C13") (pin "2") (pinfunction "2_2") (pintype "passive"))
      (node (ref "C14") (pin "2") (pinfunction "2_2") (pintype "passive"))
      (node (ref "C15") (pin "2") (pinfunction "2_2") (pintype "passive"))
      (node (ref "C16") (pin "2") (pinfunction "2_2") (pintype "passive"))
      (node (ref "C17") (pin "2") (pinfunction "2_2") (pintype "passive"))
      (node (ref "C2") (pin "1") (pinfunction "1_1") (pintype "passive"))
      (node (ref "C20") (pin "1") (pinfunction "1_1") (pintype "passive"))
      (node (ref "C22") (pin "1") (pinfunction "1_1") (pintype "passive"))
      (node (ref "C23") (pin "1") (pinfunction "1_1") (pintype "passive"))
      (node (ref "C3") (pin "1") (pinfunction "1_1") (pintype "passive"))
      (node (ref "C4") (pin "1") (pinfunction "1_1") (pintype "passive"))
      (node (ref "C5") (pin "1") (pinfunction "1_1") (pintype "passive"))
      (node (ref "C6") (pin "1") (pinfunction "1_1") (pintype "passive"))
      (node (ref "C7") (pin "2") (pinfunction "2_2") (pintype "passive"))
      (node (ref "C8") (pin "1") (pinfunction "1_1") (pintype "passive"))
      (node (ref "C9") (pin "2") (pinfunction "2_2") (pintype "passive"))
      (node (ref "D1") (pin "1") (pinfunction "A_1") (pintype "passive"))
      (node (ref "D2") (pin "1") (pinfunction "A_1") (pintype "passive"))
      (node (ref "E1") (pin "2") (pinfunction "K_2") (pintype "passive"))
      (node (ref "E2") (pin "2") (pinfunction "K_2") (pintype "passive"))
      (node (ref "E3") (pin "2") (pinfunction "K_2") (pintype "passive"))
      (node (ref "E4") (pin "2") (pinfunction "K_2") (pintype "passive"))
      (node (ref "E5") (pin "2") (pinfunction "K_2") (pintype "passive"))
      (node (ref "IC1") (pin "1") (pinfunction "GND_1") (pintype "power_in"))
      (node (ref "IC2") (pin "2") (pinfunction "GND_2") (pintype "passive"))
      (node (ref "IC2") (pin "8") (pinfunction "S_8") (pintype "passive"))
      (node (ref "IC3") (pin "15") (pinfunction "GND_15") (pintype "passive"))
      (node (ref "IC4") (pin "2") (pinfunction "GND_2") (pintype "passive"))
      (node (ref "IC4") (pin "8") (pinfunction "S_8") (pintype "passive"))
      (node (ref "JP1") (pin "2") (pinfunction "2_2") (pintype "passive"))
      (node (ref "JP11") (pin "3") (pinfunction "3_3") (pintype "passive"))
      (node (ref "JP12") (pin "4") (pinfunction "4_4") (pintype "passive"))
      (node (ref "JP13") (pin "4") (pinfunction "4_4") (pintype "passive"))
      (node (ref "JP16") (pin "3") (pinfunction "3_3") (pintype "passive"))
      (node (ref "JP17") (pin "4") (pinfunction "4_4") (pintype "passive"))
      (node (ref "JP2") (pin "3") (pinfunction "3_3") (pintype "passive"))
      (node (ref "JP20") (pin "4") (pinfunction "4_4") (pintype "passive"))
      (node (ref "JP21") (pin "3") (pinfunction "3_3") (pintype "passive"))
      (node (ref "JP21") (pin "4") (pinfunction "4_4") (pintype "passive"))
      (node (ref "JP3") (pin "2") (pinfunction "2_2") (pintype "passive"))
      (node (ref "JP4") (pin "4") (pinfunction "4_4") (pintype "passive"))
      (node (ref "JP5") (pin "10") (pinfunction "10_10") (pintype "passive"))
      (node (ref "JP5") (pin "11") (pinfunction "11_11") (pintype "passive"))
      (node (ref "JP5") (pin "12") (pinfunction "12_12") (pintype "passive"))
      (node (ref "JP5") (pin "2") (pinfunction "2_2") (pintype "passive"))
      (node (ref "JP5") (pin "3") (pinfunction "3_3") (pintype "passive"))
      (node (ref "JP5") (pin "4") (pinfunction "4_4") (pintype "passive"))
      (node (ref "JP5") (pin "5") (pinfunction "5_5") (pintype "passive"))
      (node (ref "JP5") (pin "6") (pinfunction "6_6") (pintype "passive"))
      (node (ref "JP5") (pin "7") (pinfunction "7_7") (pintype "passive"))
      (node (ref "JP5") (pin "8") (pinfunction "8_8") (pintype "passive"))
      (node (ref "JP5") (pin "9") (pinfunction "9_9") (pintype "passive"))
      (node (ref "JP8") (pin "10") (pinfunction "10_10") (pintype "passive"))
      (node (ref "JP8") (pin "11") (pinfunction "11_11") (pintype "passive"))
      (node (ref "JP8") (pin "12") (pinfunction "12_12") (pintype "passive"))
      (node (ref "JP8") (pin "2") (pinfunction "2_2") (pintype "passive"))
      (node (ref "JP8") (pin "3") (pinfunction "3_3") (pintype "passive"))
      (node (ref "JP8") (pin "4") (pinfunction "4_4") (pintype "passive"))
      (node (ref "JP8") (pin "5") (pinfunction "5_5") (pintype "passive"))
      (node (ref "JP8") (pin "6") (pinfunction "6_6") (pintype "passive"))
      (node (ref "JP8") (pin "7") (pinfunction "7_7") (pintype "passive"))
      (node (ref "JP8") (pin "8") (pinfunction "8_8") (pintype "passive"))
      (node (ref "JP8") (pin "9") (pinfunction "9_9") (pintype "passive"))
      (node (ref "LED1") (pin "2") (pinfunction "K_2") (pintype "passive"))
      (node (ref "LED2") (pin "2") (pinfunction "K_2") (pintype "passive"))
      (node (ref "R11") (pin "2") (pinfunction "2_2") (pintype "passive"))
      (node (ref "R16") (pin "1") (pinfunction "1_1") (pintype "passive"))
      (node (ref "R5") (pin "1") (pinfunction "1_1") (pintype "passive"))
      (node (ref "R6") (pin "1") (pinfunction "1_1") (pintype "passive"))
      (node (ref "R9") (pin "1") (pinfunction "1_1") (pintype "passive"))
      (node (ref "S1") (pin "1") (pinfunction "1_1") (pintype "passive"))
      (node (ref "U1") (pin "6") (pinfunction "GND_6") (pintype "passive"))
      (node (ref "U1") (pin "9") (pinfunction "POWERPAD_9") (pintype "passive"))
      (node (ref "U2") (pin "10") (pinfunction "VSS_4_10") (pintype "passive"))
      (node (ref "U2") (pin "27") (pinfunction "VSS_3_27") (pintype "passive"))
      (node (ref "U2") (pin "74") (pinfunction "VSS_2_74") (pintype "passive"))
      (node (ref "U2") (pin "99") (pinfunction "PDR_ON_99") (pintype "passive"))
      (node (ref "USB1") (pin "4") (pinfunction "GND_4") (pintype "passive"))
      (node (ref "V1") (pin "1") (pinfunction "GND_1") (pintype "passive"))
      (node (ref "X1") (pin "2") (pinfunction "2_2") (pintype "passive"))
      (node (ref "X1") (pin "4") (pinfunction "4_4") (pintype "passive"))
    )
    (net (code "70") (name "Net-(C14-Pad1)") (class "Default")
      (node (ref "C14") (pin "1") (pinfunction "1_1") (pintype "passive"))
      (node (ref "C15") (pin "1") (pinfunction "1_1") (pintype "passive"))
      (node (ref "LB1") (pin "2") (pinfunction "2_2") (pintype "passive"))
      (node (ref "R15") (pin "2") (pinfunction "2_2") (pintype "passive"))
    )
    (net (code "71") (name "Net-(D1-K)") (class "Default")
      (node (ref "C1") (pin "1") (pinfunction "1_1") (pintype "passive"))
      (node (ref "D1") (pin "2") (pinfunction "K_2") (pintype "passive"))
      (node (ref "L1") (pin "1") (pinfunction "1_1") (pintype "passive"))
      (node (ref "U1") (pin "8") (pinfunction "PH_8") (pintype "passive"))
    )
    (net (code "72") (name "Net-(D2-K)") (class "Default")
      (node (ref "D2") (pin "2") (pinfunction "K_2") (pintype "passive"))
      (node (ref "IC1") (pin "3") (pinfunction "SW_3") (pintype "bidirectional"))
      (node (ref "L2") (pin "1") (pinfunction "1_1") (pintype "passive"))
    )
    (net (code "73") (name "Net-(IC1-FB)") (class "Default")
      (node (ref "IC1") (pin "2") (pinfunction "FB_2") (pintype "input"))
      (node (ref "R2") (pin "1") (pinfunction "1_1") (pintype "passive"))
      (node (ref "R5") (pin "2") (pinfunction "2_2") (pintype "passive"))
    )
    (net (code "74") (name "Net-(IC3-C1+)") (class "Default")
      (node (ref "C19") (pin "1") (pinfunction "1_1") (pintype "passive"))
      (node (ref "IC3") (pin "1") (pinfunction "C1+_1") (pintype "passive"))
    )
    (net (code "75") (name "Net-(IC3-C1-)") (class "Default")
      (node (ref "C19") (pin "2") (pinfunction "2_2") (pintype "passive"))
      (node (ref "IC3") (pin "3") (pinfunction "C1-_3") (pintype "passive"))
    )
    (net (code "76") (name "Net-(IC3-C2+)") (class "Default")
      (node (ref "C21") (pin "2") (pinfunction "2_2") (pintype "passive"))
      (node (ref "IC3") (pin "4") (pinfunction "C2+_4") (pintype "passive"))
    )
    (net (code "77") (name "Net-(IC3-C2-)") (class "Default")
      (node (ref "C21") (pin "1") (pinfunction "1_1") (pintype "passive"))
      (node (ref "IC3") (pin "5") (pinfunction "C2-_5") (pintype "passive"))
    )
    (net (code "78") (name "Net-(IC3-V+)") (class "Default")
      (node (ref "C18") (pin "1") (pinfunction "1_1") (pintype "passive"))
      (node (ref "IC3") (pin "2") (pinfunction "V+_2") (pintype "passive"))
    )
    (net (code "79") (name "Net-(IC3-V-)") (class "Default")
      (node (ref "C22") (pin "2") (pinfunction "2_2") (pintype "passive"))
      (node (ref "IC3") (pin "6") (pinfunction "V-_6") (pintype "passive"))
    )
    (net (code "80") (name "Net-(LED1-A)") (class "Default")
      (node (ref "LED1") (pin "1") (pinfunction "A_1") (pintype "passive"))
      (node (ref "R1") (pin "1") (pinfunction "1_1") (pintype "passive"))
    )
    (net (code "81") (name "Net-(LED2-A)") (class "Default")
      (node (ref "LED2") (pin "1") (pinfunction "A_1") (pintype "passive"))
      (node (ref "R3") (pin "1") (pinfunction "1_1") (pintype "passive"))
    )
    (net (code "82") (name "Net-(LED3-A)") (class "Default")
      (node (ref "LED3") (pin "1") (pinfunction "A_1") (pintype "passive"))
      (node (ref "R12") (pin "2") (pinfunction "2_2") (pintype "passive"))
    )
    (net (code "83") (name "Net-(LED4-A)") (class "Default")
      (node (ref "LED4") (pin "1") (pinfunction "A_1") (pintype "passive"))
      (node (ref "R13") (pin "2") (pinfunction "2_2") (pintype "passive"))
    )
    (net (code "84") (name "Net-(LED5-A)") (class "Default")
      (node (ref "LED5") (pin "1") (pinfunction "A_1") (pintype "passive"))
      (node (ref "R14") (pin "2") (pinfunction "2_2") (pintype "passive"))
    )
    (net (code "85") (name "Net-(R17-Pad1)") (class "Default")
      (node (ref "R17") (pin "1") (pinfunction "1_1") (pintype "passive"))
      (node (ref "SW1") (pin "4") (pinfunction "4_4") (pintype "passive"))
    )
    (net (code "86") (name "Net-(R18-Pad1)") (class "Default")
      (node (ref "R18") (pin "1") (pinfunction "1_1") (pintype "passive"))
      (node (ref "SW1") (pin "3") (pinfunction "3_3") (pintype "passive"))
    )
    (net (code "87") (name "Net-(U1-BOOT)") (class "Default")
      (node (ref "C1") (pin "2") (pinfunction "2_2") (pintype "passive"))
      (node (ref "U1") (pin "1") (pinfunction "BOOT_1") (pintype "passive"))
    )
    (net (code "88") (name "Net-(U1-VSENSE)") (class "Default")
      (node (ref "R4") (pin "1") (pinfunction "1_1") (pintype "passive"))
      (node (ref "R6") (pin "2") (pinfunction "2_2") (pintype "passive"))
      (node (ref "U1") (pin "4") (pinfunction "VSENSE_4") (pintype "passive"))
    )
    (net (code "89") (name "Net-(U2A-PA11{slash}CAN_Rx{slash}T1C4{slash}USBDM)") (class "Default")
      (node (ref "R8") (pin "2") (pinfunction "2_2") (pintype "passive"))
      (node (ref "U2") (pin "70") (pinfunction "PA11/CAN_Rx/T1C4/USBDM_70") (pintype "passive"))
    )
    (net (code "90") (name "Net-(U2A-PA12{slash}CAN_Tx{slash}T1ETR{slash}USBDP)") (class "Default")
      (node (ref "R7") (pin "2") (pinfunction "2_2") (pintype "passive"))
      (node (ref "U2") (pin "71") (pinfunction "PA12/CAN_Tx/T1ETR/USBDP_71") (pintype "passive"))
    )
    (net (code "91") (name "Net-(U2A-PB2{slash}BOOT1)") (class "Default")
      (node (ref "R11") (pin "1") (pinfunction "1_1") (pintype "passive"))
      (node (ref "U2") (pin "37") (pinfunction "PB2/BOOT1_37") (pintype "passive"))
    )
    (net (code "92") (name "Net-(U2B-BOOT0)") (class "Default")
      (node (ref "R9") (pin "2") (pinfunction "2_2") (pintype "passive"))
      (node (ref "U2") (pin "94") (pinfunction "BOOT0_94") (pintype "passive"))
    )
    (net (code "93") (name "Net-(U2B-OSC_IN)") (class "Default")
      (node (ref "C8") (pin "2") (pinfunction "2_2") (pintype "passive"))
      (node (ref "U2") (pin "12") (pinfunction "OSC_IN_12") (pintype "passive"))
      (node (ref "X1") (pin "1") (pinfunction "1_1") (pintype "passive"))
    )
    (net (code "94") (name "Net-(U2B-OSC_OUT)") (class "Default")
      (node (ref "C4") (pin "2") (pinfunction "2_2") (pintype "passive"))
      (node (ref "U2") (pin "13") (pinfunction "OSC_OUT_13") (pintype "passive"))
      (node (ref "X1") (pin "3") (pinfunction "3_3") (pintype "passive"))
    )
    (net (code "95") (name "Net-(U2B-VCAP1)") (class "Default")
      (node (ref "C5") (pin "2") (pinfunction "2_2") (pintype "passive"))
      (node (ref "U2") (pin "49") (pinfunction "VCAP1_49") (pintype "passive"))
    )
    (net (code "96") (name "Net-(U2B-VCAP2)") (class "Default")
      (node (ref "C6") (pin "2") (pinfunction "2_2") (pintype "passive"))
      (node (ref "U2") (pin "73") (pinfunction "VCAP2_73") (pintype "passive"))
    )
    (net (code "97") (name "Net-(USB1-D-)") (class "Default")
      (node (ref "R8") (pin "1") (pinfunction "1_1") (pintype "passive"))
      (node (ref "USB1") (pin "2") (pinfunction "D-_2") (pintype "passive"))
    )
    (net (code "98") (name "VCC-3V3") (class "Default")
      (node (ref "C10") (pin "1") (pinfunction "1_1") (pintype "passive"))
      (node (ref "C11") (pin "1") (pinfunction "1_1") (pintype "passive"))
      (node (ref "C12") (pin "1") (pinfunction "1_1") (pintype "passive"))
      (node (ref "C13") (pin "1") (pinfunction "1_1") (pintype "passive"))
      (node (ref "C18") (pin "2") (pinfunction "2_2") (pintype "passive"))
      (node (ref "C9") (pin "1") (pinfunction "1_1") (pintype "passive"))
      (node (ref "E4") (pin "1") (pinfunction "A_1") (pintype "passive"))
      (node (ref "IC3") (pin "16") (pinfunction "VCC_16") (pintype "passive"))
      (node (ref "JP1") (pin "1") (pinfunction "1_1") (pintype "passive"))
      (node (ref "JP10") (pin "12") (pinfunction "12_12") (pintype "passive"))
      (node (ref "JP2") (pin "1") (pinfunction "1_1") (pintype "passive"))
      (node (ref "JP3") (pin "1") (pinfunction "1_1") (pintype "passive"))
      (node (ref "JP5") (pin "1") (pinfunction "1_1") (pintype "passive"))
      (node (ref "JP6") (pin "1") (pinfunction "1_1") (pintype "passive"))
      (node (ref "JP7") (pin "1") (pinfunction "1_1") (pintype "passive"))
      (node (ref "JP8") (pin "1") (pinfunction "1_1") (pintype "passive"))
      (node (ref "JP9") (pin "1") (pinfunction "1_1") (pintype "passive"))
      (node (ref "LB1") (pin "1") (pinfunction "1_1") (pintype "passive"))
      (node (ref "R10") (pin "1") (pinfunction "1_1") (pintype "passive"))
      (node (ref "R12") (pin "1") (pinfunction "1_1") (pintype "passive"))
      (node (ref "R13") (pin "1") (pinfunction "1_1") (pintype "passive"))
      (node (ref "R14") (pin "1") (pinfunction "1_1") (pintype "passive"))
      (node (ref "R7") (pin "1") (pinfunction "1_1") (pintype "passive"))
      (node (ref "U2") (pin "100") (pinfunction "VDD_3_100") (pintype "passive"))
      (node (ref "U2") (pin "11") (pinfunction "VDD_5_11") (pintype "passive"))
      (node (ref "U2") (pin "28") (pinfunction "VDD_4_28") (pintype "passive"))
      (node (ref "U2") (pin "50") (pinfunction "VDD_1_50") (pintype "passive"))
      (node (ref "U2") (pin "6") (pinfunction "VBAT_6") (pintype "passive"))
      (node (ref "U2") (pin "75") (pinfunction "VDD_2_75") (pintype "passive"))
      (node (ref "USB1") (pin "3") (pinfunction "D+_3") (pintype "passive"))
      (node (ref "V1") (pin "2") (pinfunction "Vout_2") (pintype "passive"))
    )
    (net (code "99") (name "VCC-5V") (class "Default")
      (node (ref "C20") (pin "2") (pinfunction "2_2") (pintype "passive"))
      (node (ref "C23") (pin "2") (pinfunction "2_2") (pintype "passive"))
      (node (ref "E3") (pin "1") (pinfunction "A_1") (pintype "passive"))
      (node (ref "E5") (pin "1") (pinfunction "A_1") (pintype "passive"))
      (node (ref "IC2") (pin "3") (pinfunction "VCC_3") (pintype "passive"))
      (node (ref "IC4") (pin "3") (pinfunction "VCC_3") (pintype "passive"))
      (node (ref "JP12") (pin "3") (pinfunction "3_3") (pintype "passive"))
      (node (ref "JP13") (pin "3") (pinfunction "3_3") (pintype "passive"))
      (node (ref "JP17") (pin "3") (pinfunction "3_3") (pintype "passive"))
      (node (ref "JP20") (pin "3") (pinfunction "3_3") (pintype "passive"))
      (node (ref "JP6") (pin "10") (pinfunction "10_10") (pintype "passive"))
      (node (ref "JP6") (pin "11") (pinfunction "11_11") (pintype "passive"))
      (node (ref "JP6") (pin "12") (pinfunction "12_12") (pintype "passive"))
      (node (ref "JP6") (pin "2") (pinfunction "2_2") (pintype "passive"))
      (node (ref "JP6") (pin "3") (pinfunction "3_3") (pintype "passive"))
      (node (ref "JP6") (pin "4") (pinfunction "4_4") (pintype "passive"))
      (node (ref "JP6") (pin "5") (pinfunction "5_5") (pintype "passive"))
      (node (ref "JP6") (pin "6") (pinfunction "6_6") (pintype "passive"))
      (node (ref "JP6") (pin "7") (pinfunction "7_7") (pintype "passive"))
      (node (ref "JP6") (pin "8") (pinfunction "8_8") (pintype "passive"))
      (node (ref "JP6") (pin "9") (pinfunction "9_9") (pintype "passive"))
      (node (ref "JP9") (pin "10") (pinfunction "10_10") (pintype "passive"))
      (node (ref "JP9") (pin "11") (pinfunction "11_11") (pintype "passive"))
      (node (ref "JP9") (pin "12") (pinfunction "12_12") (pintype "passive"))
      (node (ref "JP9") (pin "2") (pinfunction "2_2") (pintype "passive"))
      (node (ref "JP9") (pin "3") (pinfunction "3_3") (pintype "passive"))
      (node (ref "JP9") (pin "4") (pinfunction "4_4") (pintype "passive"))
      (node (ref "JP9") (pin "5") (pinfunction "5_5") (pintype "passive"))
      (node (ref "JP9") (pin "6") (pinfunction "6_6") (pintype "passive"))
      (node (ref "JP9") (pin "7") (pinfunction "7_7") (pintype "passive"))
      (node (ref "JP9") (pin "8") (pinfunction "8_8") (pintype "passive"))
      (node (ref "JP9") (pin "9") (pinfunction "9_9") (pintype "passive"))
      (node (ref "L1") (pin "2") (pinfunction "2_2") (pintype "passive"))
      (node (ref "R1") (pin "2") (pinfunction "2_2") (pintype "passive"))
      (node (ref "R4") (pin "2") (pinfunction "2_2") (pintype "passive"))
      (node (ref "USB1") (pin "1") (pinfunction "VCC_1") (pintype "passive"))
      (node (ref "V1") (pin "3") (pinfunction "Vin_3") (pintype "passive"))
    )
    (net (code "100") (name "VCC-6.3V") (class "Default")
      (node (ref "E1") (pin "1") (pinfunction "A_1") (pintype "passive"))
      (node (ref "L2") (pin "2") (pinfunction "2_2") (pintype "passive"))
      (node (ref "R2") (pin "2") (pinfunction "2_2") (pintype "passive"))
      (node (ref "R3") (pin "2") (pinfunction "2_2") (pintype "passive"))
    )
    (net (code "101") (name "VCC-12V") (class "Default")
      (node (ref "C2") (pin "2") (pinfunction "2_2") (pintype "passive"))
      (node (ref "C3") (pin "2") (pinfunction "2_2") (pintype "passive"))
      (node (ref "E2") (pin "1") (pinfunction "A_1") (pintype "passive"))
      (node (ref "IC1") (pin "4") (pinfunction "EN_4") (pintype "input"))
      (node (ref "IC1") (pin "5") (pinfunction "VIN_5") (pintype "power_in"))
      (node (ref "JP21") (pin "1") (pinfunction "1_1") (pintype "passive"))
      (node (ref "JP21") (pin "2") (pinfunction "2_2") (pintype "passive"))
      (node (ref "U1") (pin "7") (pinfunction "VIN_7") (pintype "passive"))
    )
    (net (code "102") (name "unconnected-(IC2-VREF-Pad5)") (class "Default")
      (node (ref "IC2") (pin "5") (pinfunction "VREF_5") (pintype "passive+no_connect"))
    )
    (net (code "103") (name "unconnected-(IC4-VREF-Pad5)") (class "Default")
      (node (ref "IC4") (pin "5") (pinfunction "VREF_5") (pintype "passive+no_connect"))
    )
    (net (code "104") (name "unconnected-(U1-ENA-Pad5)") (class "Default")
      (node (ref "U1") (pin "5") (pinfunction "ENA_5") (pintype "passive"))
    )
    (net (code "105") (name "unconnected-(U1-NC-Pad2)") (class "Default")
      (node (ref "U1") (pin "2") (pinfunction "NC_2") (pintype "passive+no_connect"))
    )
    (net (code "106") (name "unconnected-(U1-NC-Pad3)") (class "Default")
      (node (ref "U1") (pin "3") (pinfunction "NC_3") (pintype "passive+no_connect"))
    )
    (net (code "107") (name "unconnected-(U2A-PA6{slash}ADC123_IN6{slash}SPI1_MISO{slash}T8T1BKIN{slash}T3C1-Pad31)") (class "Default")
      (node (ref "U2") (pin "31") (pinfunction "PA6/ADC123_IN6/SPI1_MISO/T8T1BKIN/T3C1_31") (pintype "passive"))
    )
    (net (code "108") (name "unconnected-(U2A-PA8{slash}T1C1{slash}MCO-Pad67)") (class "Default")
      (node (ref "U2") (pin "67") (pinfunction "PA8/T1C1/MCO_67") (pintype "passive"))
    )
    (net (code "109") (name "unconnected-(U2A-PA15{slash}JTDI{slash}I2S3_WS{slash}JTDI{slash}T2C1ETR{slash}SPI3_NSS-Pad75)") (class "Default")
      (node (ref "U2") (pin "75") (pinfunction "PA15/JTDI/I2S3_WS/JTDI/T2C1ETR/SPI3_NSS_75") (pintype "passive"))
    )
    (net (code "110") (name "unconnected-(U2A-PB0{slash}ADC123_IN8{slash}T3C3{slash}T8C2N{slash}T1C2N-Pad35)") (class "Default")
      (node (ref "U2") (pin "35") (pinfunction "PB0/ADC123_IN8/T3C3/T8C2N/T1C2N_35") (pintype "passive"))
    )
    (net (code "111") (name "unconnected-(U2A-PB14{slash}T1CH2N{slash}SPI2_MISO-Pad53)") (class "Default")
      (node (ref "U2") (pin "53") (pinfunction "PB14/T1CH2N/SPI2_MISO_53") (pintype "passive"))
    )
    (net (code "112") (name "unconnected-(U2A-PB15{slash}I2S2_SD{slash}T1CH3N{slash}SPI2_MOSI-Pad54)") (class "Default")
      (node (ref "U2") (pin "54") (pinfunction "PB15/I2S2_SD/T1CH3N/SPI2_MOSI_54") (pintype "passive"))
    )
    (net (code "113") (name "unconnected-(U2A-PC0{slash}ADC123_IN10-Pad15)") (class "Default")
      (node (ref "U2") (pin "15") (pinfunction "PC0/ADC123_IN10_15") (pintype "passive"))
    )
    (net (code "114") (name "unconnected-(U2A-PC1{slash}ADC123_IN11-Pad16)") (class "Default")
      (node (ref "U2") (pin "16") (pinfunction "PC1/ADC123_IN11_16") (pintype "passive"))
    )
    (net (code "115") (name "unconnected-(U2A-PC2{slash}ADC123_IN12-Pad17)") (class "Default")
      (node (ref "U2") (pin "17") (pinfunction "PC2/ADC123_IN12_17") (pintype "passive"))
    )
    (net (code "116") (name "unconnected-(U2A-PC9{slash}T8C4{slash}T3C4{slash}SDIO_D1-Pad66)") (class "Default")
      (node (ref "U2") (pin "66") (pinfunction "PC9/T8C4/T3C4/SDIO_D1_66") (pintype "passive"))
    )
    (net (code "117") (name "unconnected-(U2A-PD12{slash}T4C1{slash}FSMC_A17-Pad59)") (class "Default")
      (node (ref "U2") (pin "59") (pinfunction "PD12/T4C1/FSMC_A17_59") (pintype "passive"))
    )
    (net (code "118") (name "unconnected-(U2A-PD13{slash}T4C2{slash}FSMC_A18-Pad60)") (class "Default")
      (node (ref "U2") (pin "60") (pinfunction "PD13/T4C2/FSMC_A18_60") (pintype "passive"))
    )
    (net (code "119") (name "unconnected-(U2A-PD14{slash}T4C3{slash}FSMC_D0-Pad61)") (class "Default")
      (node (ref "U2") (pin "61") (pinfunction "PD14/T4C3/FSMC_D0_61") (pintype "passive"))
    )
    (net (code "120") (name "unconnected-(U2A-PE2{slash}TRACECK{slash}FSMC_A23-Pad1)") (class "Default")
      (node (ref "U2") (pin "1") (pinfunction "PE2/TRACECK/FSMC_A23_1") (pintype "passive"))
    )
    (net (code "121") (name "unconnected-(U2A-PE3{slash}TRACED0{slash}FSMC_A19-Pad2)") (class "Default")
      (node (ref "U2") (pin "2") (pinfunction "PE3/TRACED0/FSMC_A19_2") (pintype "passive"))
    )
    (net (code "122") (name "unconnected-(U2A-PE4{slash}TRACED1{slash}FSMC_A20-Pad3)") (class "Default")
      (node (ref "U2") (pin "3") (pinfunction "PE4/TRACED1/FSMC_A20_3") (pintype "passive"))
    )
    (net (code "123") (name "unconnected-(U2A-PE5{slash}TRACED2{slash}FSMC_A21-Pad4)") (class "Default")
      (node (ref "U2") (pin "4") (pinfunction "PE5/TRACED2/FSMC_A21_4") (pintype "passive"))
    )
    (net (code "124") (name "unconnected-(U2A-PE6{slash}TRACED3{slash}FSMC_A22-Pad5)") (class "Default")
      (node (ref "U2") (pin "5") (pinfunction "PE6/TRACED3/FSMC_A22_5") (pintype "passive"))
    )
    (net (code "125") (name "unconnected-(U2B-PC14-OSC32_IN-Pad8)") (class "Default")
      (node (ref "U2") (pin "8") (pinfunction "PC14-OSC32_IN_8") (pintype "passive+no_connect"))
    )
    (net (code "126") (name "unconnected-(U2B-PC15-OSC32_OUT-Pad9)") (class "Default")
      (node (ref "U2") (pin "9") (pinfunction "PC15-OSC32_OUT_9") (pintype "passive+no_connect"))
    )
  )
)
